# cruise.net
KiCad netlist of a schematic drawn in EAGLE
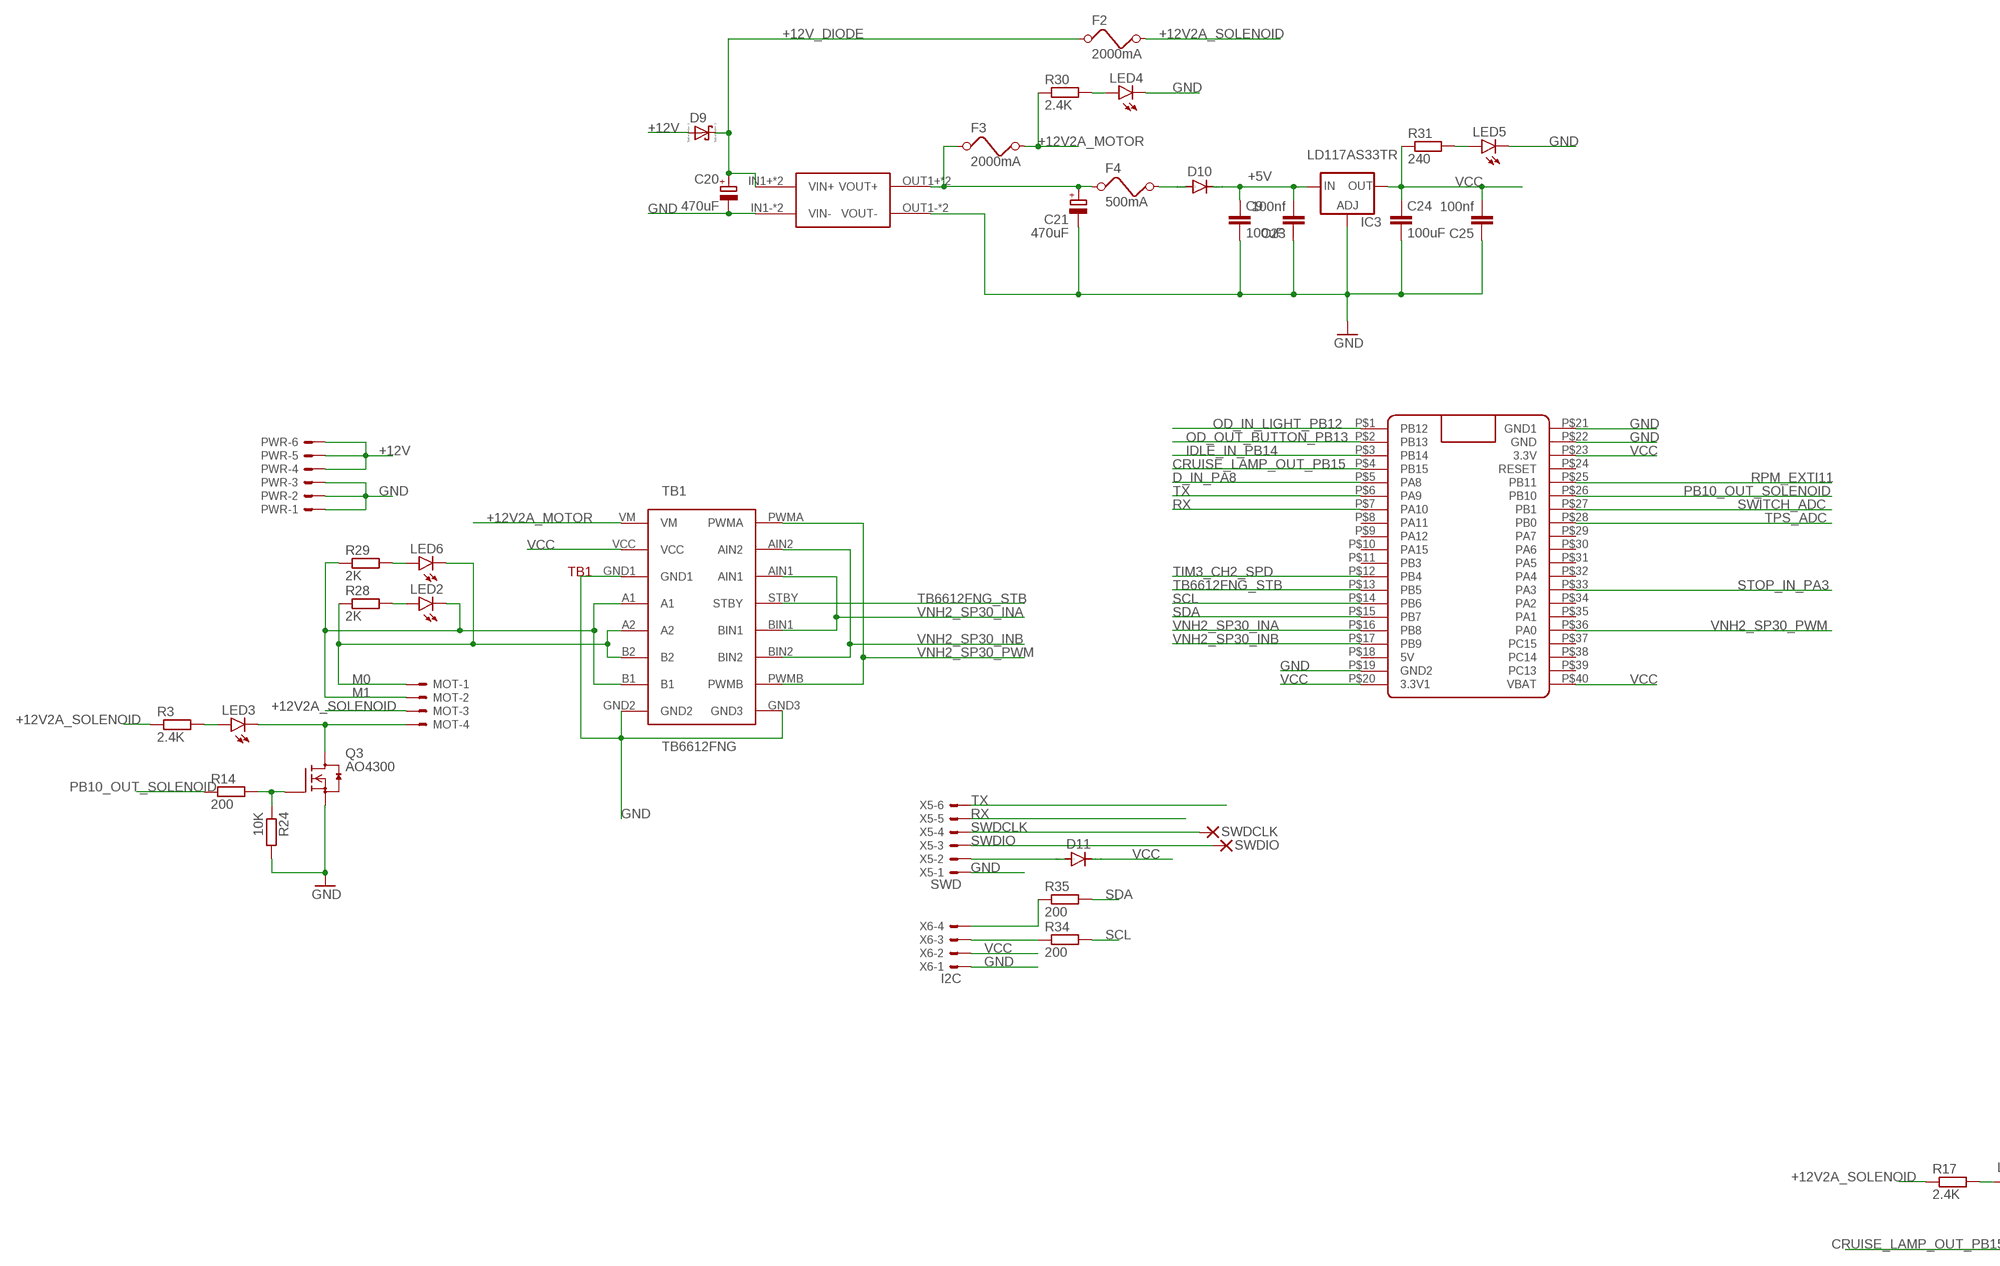
[diagram p0: schematic, sheet 1, part 1 of 2]
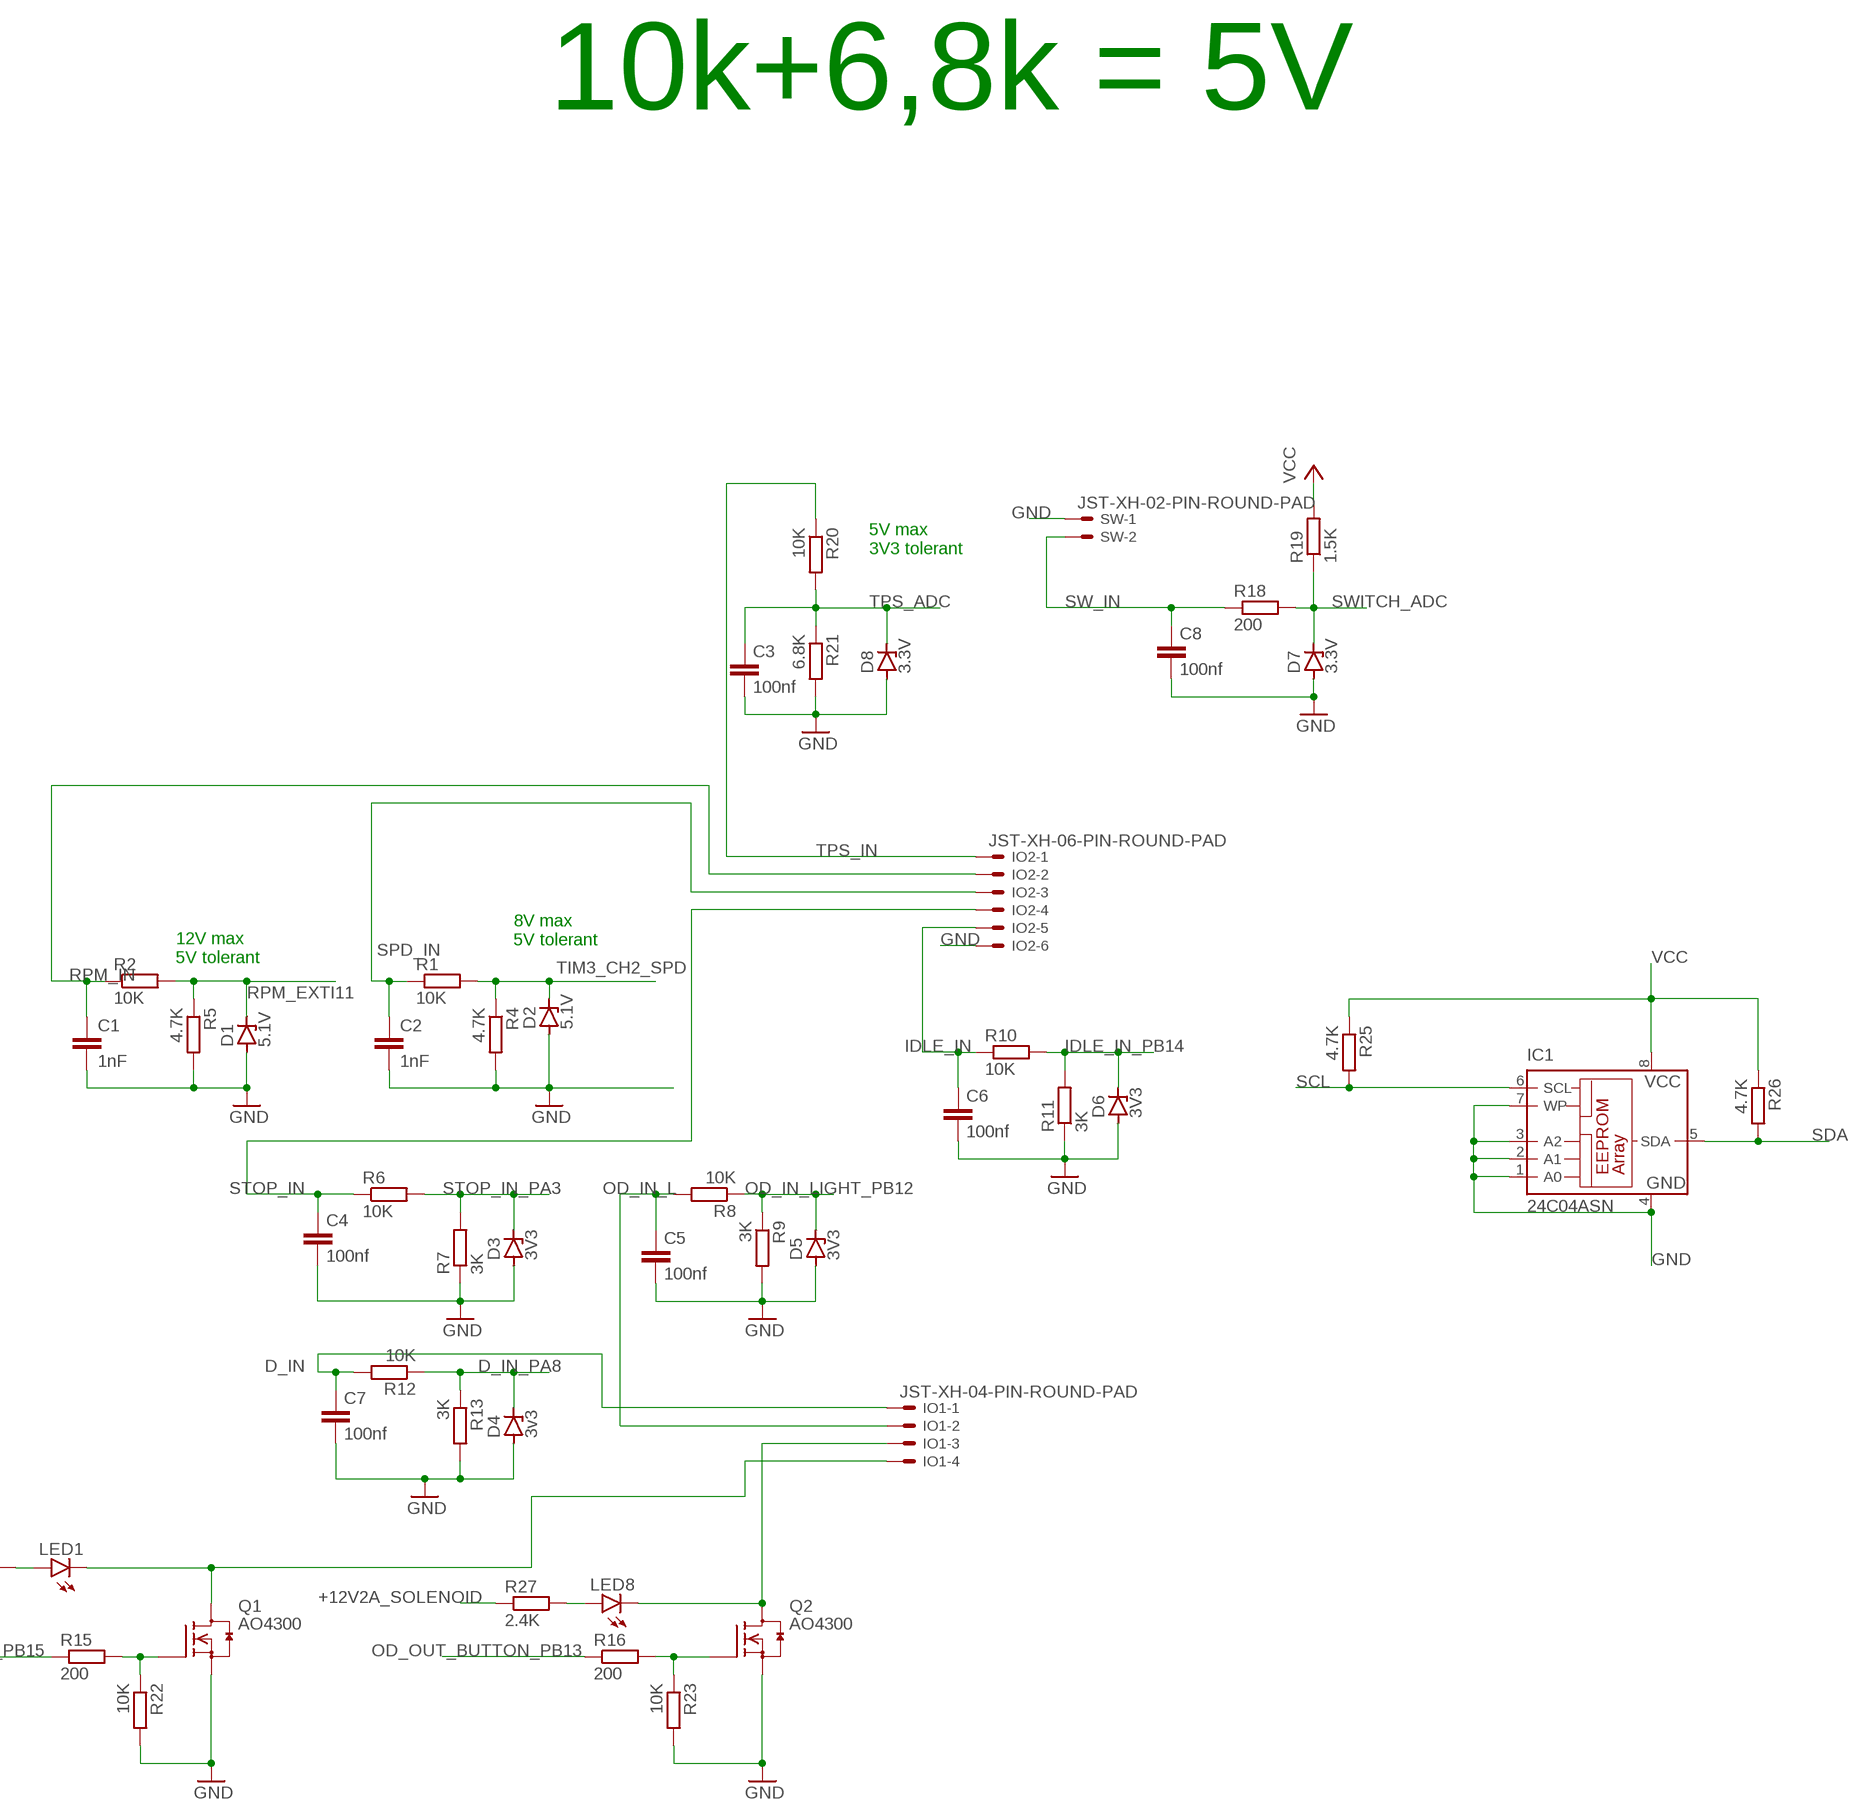
[diagram p1: schematic, sheet 1, part 2 of 2]

(export (version "E")
  (design (tool "Eeschema 10.0.6"))
  (components
    (comp (ref "C1")
      (value "1nF")
      (footprint "eagle-import:C0805K")
      (libsource (lib "eagle-import") (part "C-EUC0805K"))
    )
    (comp (ref "C2")
      (value "1nF")
      (footprint "eagle-import:C0805K")
      (libsource (lib "eagle-import") (part "C-EUC0805K"))
    )
    (comp (ref "C3")
      (value "100nf")
      (footprint "eagle-import:C0805K")
      (libsource (lib "eagle-import") (part "C-EUC0805K"))
    )
    (comp (ref "C4")
      (value "100nf")
      (footprint "eagle-import:C0805K")
      (libsource (lib "eagle-import") (part "C-EUC0805K"))
    )
    (comp (ref "C5")
      (value "100nf")
      (footprint "eagle-import:C0805K")
      (libsource (lib "eagle-import") (part "C-EUC0805K"))
    )
    (comp (ref "C6")
      (value "100nf")
      (footprint "eagle-import:C0805K")
      (libsource (lib "eagle-import") (part "C-EUC0805K"))
    )
    (comp (ref "C7")
      (value "100nf")
      (footprint "eagle-import:C0805K")
      (libsource (lib "eagle-import") (part "C-EUC0805K"))
    )
    (comp (ref "C8")
      (value "100nf")
      (footprint "eagle-import:C0805K")
      (libsource (lib "eagle-import") (part "C-EUC0805K"))
    )
    (comp (ref "C9")
      (value "100uF")
      (footprint "eagle-import:C1210")
      (libsource (lib "eagle-import") (part "resistor_348_C-EUC1210"))
    )
    (comp (ref "C20")
      (value "470uF")
      (footprint "eagle-import:PANASONIC_G")
      (libsource (lib "eagle-import") (part "CPOL-EUG"))
    )
    (comp (ref "C21")
      (value "470uF")
      (footprint "eagle-import:PANASONIC_G")
      (libsource (lib "eagle-import") (part "CPOL-EUG"))
    )
    (comp (ref "C23")
      (value "100nf")
      (footprint "eagle-import:C0805")
      (libsource (lib "eagle-import") (part "C-EUC0805"))
    )
    (comp (ref "C24")
      (value "100uF")
      (footprint "eagle-import:C1210")
      (libsource (lib "eagle-import") (part "resistor_348_C-EUC1210"))
    )
    (comp (ref "C25")
      (value "100nf")
      (footprint "eagle-import:C0805")
      (libsource (lib "eagle-import") (part "C-EUC0805"))
    )
    (comp (ref "D1")
      (value "5.1V")
      (footprint "eagle-import:SOD80C")
      (libsource (lib "eagle-import") (part "ZENER-DIODESOD80C"))
    )
    (comp (ref "D2")
      (value "5.1V")
      (footprint "eagle-import:SOD80C")
      (libsource (lib "eagle-import") (part "ZENER-DIODESOD80C"))
    )
    (comp (ref "D3")
      (value "3V3")
      (footprint "eagle-import:SOD80C")
      (libsource (lib "eagle-import") (part "ZENER-DIODESOD80C"))
    )
    (comp (ref "D4")
      (value "3v3")
      (footprint "eagle-import:SOD80C")
      (libsource (lib "eagle-import") (part "ZENER-DIODESOD80C"))
    )
    (comp (ref "D5")
      (value "3V3")
      (footprint "eagle-import:SOD80C")
      (libsource (lib "eagle-import") (part "ZENER-DIODESOD80C"))
    )
    (comp (ref "D6")
      (value "3V3")
      (footprint "eagle-import:SOD80C")
      (libsource (lib "eagle-import") (part "ZENER-DIODESOD80C"))
    )
    (comp (ref "D7")
      (value "3.3V")
      (footprint "eagle-import:SOD80C")
      (libsource (lib "eagle-import") (part "ZENER-DIODESOD80C"))
    )
    (comp (ref "D8")
      (value "3.3V")
      (footprint "eagle-import:SOD80C")
      (libsource (lib "eagle-import") (part "ZENER-DIODESOD80C"))
    )
    (comp (ref "D9")
      (value "SCHOTTKY-DIODESMC")
      (footprint "eagle-import:DIODE_SMC")
      (libsource (lib "eagle-import") (part "SCHOTTKY-DIODESMC"))
    )
    (comp (ref "D10")
      (value "DIODE-SOD323-W")
      (footprint "eagle-import:SOD323-W")
      (libsource (lib "eagle-import") (part "DIODE-SOD323-W"))
    )
    (comp (ref "D11")
      (value "DIODE-SOD323-W")
      (footprint "eagle-import:SOD323-W")
      (libsource (lib "eagle-import") (part "DIODE-SOD323-W"))
    )
    (comp (ref "F2")
      (value "2000mA")
      (footprint "eagle-import:1206")
      (libsource (lib "eagle-import") (part "FUSEC"))
    )
    (comp (ref "F3")
      (value "2000mA")
      (footprint "eagle-import:1206")
      (libsource (lib "eagle-import") (part "FUSEC"))
    )
    (comp (ref "F4")
      (value "500mA")
      (footprint "eagle-import:1206")
      (libsource (lib "eagle-import") (part "FUSEC"))
    )
    (comp (ref "IC1")
      (value "24C04ASN")
      (footprint "eagle-import:SO-08")
      (libsource (lib "eagle-import") (part "24CSN04A"))
    )
    (comp (ref "IC3")
      (value "LD117AS33TR")
      (footprint "eagle-import:SOT223")
      (libsource (lib "eagle-import") (part "LD117A?S33TR"))
    )
    (comp (ref "IO1")
      (value "JST-XH-04-PIN-ROUND-PAD")
      (footprint "eagle-import:JST-XH-04-PACKAGE-ROUND-PAD")
      (libsource (lib "eagle-import") (part "JST-XH-04-PIN-ROUND-PAD"))
    )
    (comp (ref "IO2")
      (value "JST-XH-06-PIN-ROUND-PAD")
      (footprint "eagle-import:JST-XH-06-PACKAGE-ROUND-PAD")
      (libsource (lib "eagle-import") (part "JST-XH-06-PIN-ROUND-PAD"))
    )
    (comp (ref "LED1")
      (value "LED3MM")
      (footprint "eagle-import:LED3MM")
      (libsource (lib "eagle-import") (part "LED3MM"))
    )
    (comp (ref "LED2")
      (value "LED3MM")
      (footprint "eagle-import:LED3MM")
      (libsource (lib "eagle-import") (part "LED3MM"))
    )
    (comp (ref "LED3")
      (value "LED3MM")
      (footprint "eagle-import:LED3MM")
      (libsource (lib "eagle-import") (part "LED3MM"))
    )
    (comp (ref "LED4")
      (value "LED3MM")
      (footprint "eagle-import:LED3MM")
      (libsource (lib "eagle-import") (part "LED3MM"))
    )
    (comp (ref "LED5")
      (value "LED3MM")
      (footprint "eagle-import:LED3MM")
      (libsource (lib "eagle-import") (part "LED3MM"))
    )
    (comp (ref "LED6")
      (value "LED3MM")
      (footprint "eagle-import:LED3MM")
      (libsource (lib "eagle-import") (part "LED3MM"))
    )
    (comp (ref "LED8")
      (value "LED3MM")
      (footprint "eagle-import:LED3MM")
      (libsource (lib "eagle-import") (part "LED3MM"))
    )
    (comp (ref "MOT")
      (value "JST-XH-04-PIN-LONG-PAD")
      (footprint "eagle-import:JST-XH-04-PACKAGE-LONG-PAD")
      (libsource (lib "eagle-import") (part "JST-XH-04-PIN-LONG-PAD"))
    )
    (comp (ref "PWR")
      (value "JST-XH-06-PIN-LONG-PAD")
      (footprint "eagle-import:JST-XH-06-PACKAGE-LONG-PAD")
      (libsource (lib "eagle-import") (part "JST-XH-06-PIN-LONG-PAD"))
    )
    (comp (ref "Q1")
      (value "AO4300")
      (footprint "eagle-import:SOT23")
      (libsource (lib "eagle-import") (part "BSS138"))
    )
    (comp (ref "Q2")
      (value "AO4300")
      (footprint "eagle-import:SOT23")
      (libsource (lib "eagle-import") (part "BSS138"))
    )
    (comp (ref "Q3")
      (value "AO4300")
      (footprint "eagle-import:SOT23")
      (libsource (lib "eagle-import") (part "BSS138"))
    )
    (comp (ref "R1")
      (value "10K")
      (footprint "eagle-import:R0805")
      (libsource (lib "eagle-import") (part "R-EU_R0805"))
    )
    (comp (ref "R2")
      (value "10K")
      (footprint "eagle-import:R0805")
      (libsource (lib "eagle-import") (part "R-EU_R0805"))
    )
    (comp (ref "R3")
      (value "2.4K")
      (footprint "eagle-import:R0805")
      (libsource (lib "eagle-import") (part "R-EU_R0805"))
    )
    (comp (ref "R4")
      (value "4.7K")
      (footprint "eagle-import:R0805")
      (libsource (lib "eagle-import") (part "R-EU_R0805"))
    )
    (comp (ref "R5")
      (value "4.7K")
      (footprint "eagle-import:R0805")
      (libsource (lib "eagle-import") (part "R-EU_R0805"))
    )
    (comp (ref "R6")
      (value "10K")
      (footprint "eagle-import:R0805")
      (libsource (lib "eagle-import") (part "R-EU_R0805"))
    )
    (comp (ref "R7")
      (value "3K")
      (footprint "eagle-import:R0805")
      (libsource (lib "eagle-import") (part "R-EU_R0805"))
    )
    (comp (ref "R8")
      (value "10K")
      (footprint "eagle-import:R0805")
      (libsource (lib "eagle-import") (part "R-EU_R0805"))
    )
    (comp (ref "R9")
      (value "3K")
      (footprint "eagle-import:R0805")
      (libsource (lib "eagle-import") (part "R-EU_R0805"))
    )
    (comp (ref "R10")
      (value "10K")
      (footprint "eagle-import:R0805")
      (libsource (lib "eagle-import") (part "R-EU_R0805"))
    )
    (comp (ref "R11")
      (value "3K")
      (footprint "eagle-import:R0805")
      (libsource (lib "eagle-import") (part "R-EU_R0805"))
    )
    (comp (ref "R12")
      (value "10K")
      (footprint "eagle-import:R0805")
      (libsource (lib "eagle-import") (part "R-EU_R0805"))
    )
    (comp (ref "R13")
      (value "3K")
      (footprint "eagle-import:R0805")
      (libsource (lib "eagle-import") (part "R-EU_R0805"))
    )
    (comp (ref "R14")
      (value "200")
      (footprint "eagle-import:R0805")
      (libsource (lib "eagle-import") (part "R-EU_R0805"))
    )
    (comp (ref "R15")
      (value "200")
      (footprint "eagle-import:R0805")
      (libsource (lib "eagle-import") (part "R-EU_R0805"))
    )
    (comp (ref "R16")
      (value "200")
      (footprint "eagle-import:R0805")
      (libsource (lib "eagle-import") (part "R-EU_R0805"))
    )
    (comp (ref "R17")
      (value "2.4K")
      (footprint "eagle-import:R0805")
      (libsource (lib "eagle-import") (part "R-EU_R0805"))
    )
    (comp (ref "R18")
      (value "200")
      (footprint "eagle-import:R0805")
      (libsource (lib "eagle-import") (part "R-EU_R0805"))
    )
    (comp (ref "R19")
      (value "1.5K")
      (footprint "eagle-import:R0805")
      (libsource (lib "eagle-import") (part "R-EU_R0805"))
    )
    (comp (ref "R20")
      (value "10K")
      (footprint "eagle-import:R0805")
      (libsource (lib "eagle-import") (part "R-EU_R0805"))
    )
    (comp (ref "R21")
      (value "6.8K")
      (footprint "eagle-import:R0805")
      (libsource (lib "eagle-import") (part "R-EU_R0805"))
    )
    (comp (ref "R22")
      (value "10K")
      (footprint "eagle-import:R0805")
      (libsource (lib "eagle-import") (part "R-EU_R0805"))
    )
    (comp (ref "R23")
      (value "10K")
      (footprint "eagle-import:R0805")
      (libsource (lib "eagle-import") (part "R-EU_R0805"))
    )
    (comp (ref "R24")
      (value "10K")
      (footprint "eagle-import:R0805")
      (libsource (lib "eagle-import") (part "R-EU_R0805"))
    )
    (comp (ref "R25")
      (value "4.7K")
      (footprint "eagle-import:R0805")
      (libsource (lib "eagle-import") (part "R-EU_R0805"))
    )
    (comp (ref "R26")
      (value "4.7K")
      (footprint "eagle-import:R0805")
      (libsource (lib "eagle-import") (part "R-EU_R0805"))
    )
    (comp (ref "R27")
      (value "2.4K")
      (footprint "eagle-import:R0805")
      (libsource (lib "eagle-import") (part "R-EU_R0805"))
    )
    (comp (ref "R28")
      (value "2K")
      (footprint "eagle-import:R0805")
      (libsource (lib "eagle-import") (part "R-EU_R0805"))
    )
    (comp (ref "R29")
      (value "2K")
      (footprint "eagle-import:R0805")
      (libsource (lib "eagle-import") (part "R-EU_R0805"))
    )
    (comp (ref "R30")
      (value "2.4K")
      (footprint "eagle-import:R0805")
      (libsource (lib "eagle-import") (part "R-EU_R0805"))
    )
    (comp (ref "R31")
      (value "240")
      (footprint "eagle-import:R0805")
      (libsource (lib "eagle-import") (part "R-EU_R0805"))
    )
    (comp (ref "R34")
      (value "200")
      (footprint "eagle-import:R0805")
      (libsource (lib "eagle-import") (part "R-EU_R0805"))
    )
    (comp (ref "R35")
      (value "200")
      (footprint "eagle-import:R0805")
      (libsource (lib "eagle-import") (part "R-EU_R0805"))
    )
    (comp (ref "SW")
      (value "JST-XH-02-PIN-ROUND-PAD")
      (footprint "eagle-import:JST-XH-02-PACKAGE-ROUND-PAD")
      (libsource (lib "eagle-import") (part "JST-XH-02-PIN-ROUND-PAD"))
    )
    (comp (ref "SWDCLK")
      (value "WIREPAD2,15/1,0")
      (footprint "eagle-import:2,15_1,0")
      (libsource (lib "eagle-import") (part "WIREPAD2,15/1,0"))
    )
    (comp (ref "SWDIO")
      (value "WIREPAD2,15/1,0")
      (footprint "eagle-import:2,15_1,0")
      (libsource (lib "eagle-import") (part "WIREPAD2,15/1,0"))
    )
    (comp (ref "TB1")
      (value "TB6612FNG")
      (footprint "eagle-import:TB6612FNG")
      (libsource (lib "eagle-import") (part "TB6612FNG"))
    )
    (comp (ref "U$1")
      (value "BLUE_PILL")
      (footprint "eagle-import:BLUE_PILL")
      (libsource (lib "eagle-import") (part "BLUE_PILL"))
    )
    (comp (ref "U$6")
      (value "MP1584")
      (footprint "eagle-import:DC-BRICK")
      (libsource (lib "eagle-import") (part "MP1584"))
    )
    (comp (ref "X5")
      (value "SWD")
      (footprint "eagle-import:JST-XH-06-PACKAGE-ROUND-PAD")
      (libsource (lib "eagle-import") (part "JST-XH-06-PIN-ROUND-PAD"))
    )
    (comp (ref "X6")
      (value "I2C")
      (footprint "eagle-import:JST-XH-04-PACKAGE-ROUND-PAD")
      (libsource (lib "eagle-import") (part "JST-XH-04-PIN-ROUND-PAD"))
    )
  )
  (nets
    (net (code "1") (name "/+5V") (class "Default")
      (node (ref "C23") (pin "2") (pinfunction "2_2") (pintype "passive"))
      (node (ref "C9") (pin "1") (pinfunction "1_1") (pintype "passive"))
      (node (ref "D10") (pin "C") (pinfunction "C_C") (pintype "passive"))
      (node (ref "IC3") (pin "3") (pinfunction "IN_3") (pintype "input"))
    )
    (net (code "2") (name "/+12V") (class "Default")
      (node (ref "D9") (pin "A") (pinfunction "C_A") (pintype "passive"))
      (node (ref "PWR") (pin "4") (pinfunction "S_4") (pintype "passive"))
      (node (ref "PWR") (pin "5") (pinfunction "S_5") (pintype "passive"))
      (node (ref "PWR") (pin "6") (pinfunction "S_6") (pintype "passive"))
    )
    (net (code "3") (name "/+12V2A_MOTOR") (class "Default")
      (node (ref "F3") (pin "2") (pinfunction "2_2") (pintype "passive"))
      (node (ref "R30") (pin "1") (pinfunction "1_1") (pintype "passive"))
      (node (ref "TB1") (pin "VM") (pinfunction "VM_VM") (pintype "bidirectional"))
    )
    (net (code "4") (name "/+12V2A_SOLENOID") (class "Default")
      (node (ref "F2") (pin "2") (pinfunction "2_2") (pintype "passive"))
      (node (ref "MOT") (pin "3") (pinfunction "S_3") (pintype "passive"))
      (node (ref "R17") (pin "1") (pinfunction "1_1") (pintype "passive"))
      (node (ref "R27") (pin "1") (pinfunction "1_1") (pintype "passive"))
      (node (ref "R3") (pin "1") (pinfunction "1_1") (pintype "passive"))
    )
    (net (code "5") (name "/+12V_DIODE") (class "Default")
      (node (ref "C20") (pin "+") (pinfunction "+_+") (pintype "passive"))
      (node (ref "D9") (pin "C") (pinfunction "A_C") (pintype "passive"))
      (node (ref "F2") (pin "1") (pinfunction "1_1") (pintype "passive"))
      (node (ref "U$6") (pin "IN1+") (pinfunction "VIN+_IN1+") (pintype "input"))
      (node (ref "U$6") (pin "IN2+") (pinfunction "VIN+_IN2+") (pintype "input"))
    )
    (net (code "6") (name "/CRUISE_LAMP_OUT_PB15") (class "Default")
      (node (ref "R15") (pin "1") (pinfunction "1_1") (pintype "passive"))
      (node (ref "U$1") (pin "P$4") (pinfunction "PB15_P$4") (pintype "bidirectional"))
    )
    (net (code "7") (name "/D_IN") (class "Default")
      (node (ref "C7") (pin "1") (pinfunction "1_1") (pintype "passive"))
      (node (ref "IO1") (pin "1") (pinfunction "S_1") (pintype "passive"))
      (node (ref "R12") (pin "2") (pinfunction "2_2") (pintype "passive"))
    )
    (net (code "8") (name "/D_IN_PA8") (class "Default")
      (node (ref "D4") (pin "C") (pinfunction "C_C") (pintype "passive"))
      (node (ref "R12") (pin "1") (pinfunction "1_1") (pintype "passive"))
      (node (ref "R13") (pin "1") (pinfunction "1_1") (pintype "passive"))
      (node (ref "U$1") (pin "P$5") (pinfunction "PA8_P$5") (pintype "bidirectional"))
    )
    (net (code "9") (name "/IDLE_IN") (class "Default")
      (node (ref "C6") (pin "1") (pinfunction "1_1") (pintype "passive"))
      (node (ref "IO2") (pin "5") (pinfunction "S_5") (pintype "passive"))
      (node (ref "R10") (pin "1") (pinfunction "1_1") (pintype "passive"))
    )
    (net (code "10") (name "/IDLE_IN_PB14") (class "Default")
      (node (ref "D6") (pin "C") (pinfunction "C_C") (pintype "passive"))
      (node (ref "R10") (pin "2") (pinfunction "2_2") (pintype "passive"))
      (node (ref "R11") (pin "2") (pinfunction "2_2") (pintype "passive"))
      (node (ref "U$1") (pin "P$3") (pinfunction "PB14_P$3") (pintype "bidirectional"))
    )
    (net (code "11") (name "/M0") (class "Default")
      (node (ref "LED6") (pin "K") (pinfunction "C_K") (pintype "passive"))
      (node (ref "MOT") (pin "1") (pinfunction "S_1") (pintype "passive"))
      (node (ref "R28") (pin "1") (pinfunction "1_1") (pintype "passive"))
      (node (ref "TB1") (pin "A2") (pinfunction "A2_A2") (pintype "bidirectional"))
      (node (ref "TB1") (pin "B2") (pinfunction "B2_B2") (pintype "bidirectional"))
    )
    (net (code "12") (name "/M1") (class "Default")
      (node (ref "LED2") (pin "K") (pinfunction "C_K") (pintype "passive"))
      (node (ref "MOT") (pin "2") (pinfunction "S_2") (pintype "passive"))
      (node (ref "R29") (pin "1") (pinfunction "1_1") (pintype "passive"))
      (node (ref "TB1") (pin "A1") (pinfunction "A1_A1") (pintype "bidirectional"))
      (node (ref "TB1") (pin "B1") (pinfunction "B1_B1") (pintype "bidirectional"))
    )
    (net (code "13") (name "/OD_IN_L") (class "Default")
      (node (ref "C5") (pin "1") (pinfunction "1_1") (pintype "passive"))
      (node (ref "IO1") (pin "2") (pinfunction "S_2") (pintype "passive"))
      (node (ref "R8") (pin "2") (pinfunction "2_2") (pintype "passive"))
    )
    (net (code "14") (name "/OD_IN_LIGHT_PB12") (class "Default")
      (node (ref "D5") (pin "C") (pinfunction "C_C") (pintype "passive"))
      (node (ref "R8") (pin "1") (pinfunction "1_1") (pintype "passive"))
      (node (ref "R9") (pin "1") (pinfunction "1_1") (pintype "passive"))
      (node (ref "U$1") (pin "P$1") (pinfunction "PB12_P$1") (pintype "bidirectional"))
    )
    (net (code "15") (name "/OD_OUT_BUTTON_PB13") (class "Default")
      (node (ref "R16") (pin "1") (pinfunction "1_1") (pintype "passive"))
      (node (ref "U$1") (pin "P$2") (pinfunction "PB13_P$2") (pintype "bidirectional"))
    )
    (net (code "16") (name "/PB10_OUT_SOLENOID") (class "Default")
      (node (ref "R14") (pin "1") (pinfunction "1_1") (pintype "passive"))
      (node (ref "U$1") (pin "P$26") (pinfunction "PB10_P$26") (pintype "bidirectional"))
    )
    (net (code "17") (name "/RPM_EXTI11") (class "Default")
      (node (ref "D1") (pin "C") (pinfunction "C_C") (pintype "passive"))
      (node (ref "R2") (pin "2") (pinfunction "2_2") (pintype "passive"))
      (node (ref "R5") (pin "1") (pinfunction "1_1") (pintype "passive"))
      (node (ref "U$1") (pin "P$25") (pinfunction "PB11_P$25") (pintype "bidirectional"))
    )
    (net (code "18") (name "/RPM_IN") (class "Default")
      (node (ref "C1") (pin "1") (pinfunction "1_1") (pintype "passive"))
      (node (ref "IO2") (pin "2") (pinfunction "S_2") (pintype "passive"))
      (node (ref "R2") (pin "1") (pinfunction "1_1") (pintype "passive"))
    )
    (net (code "19") (name "/RX") (class "Default")
      (node (ref "U$1") (pin "P$7") (pinfunction "PA10_P$7") (pintype "bidirectional"))
      (node (ref "X5") (pin "5") (pinfunction "S_5") (pintype "passive"))
    )
    (net (code "20") (name "/SCL") (class "Default")
      (node (ref "IC1") (pin "6") (pinfunction "SCL_6") (pintype "input"))
      (node (ref "R25") (pin "2") (pinfunction "2_2") (pintype "passive"))
      (node (ref "R34") (pin "2") (pinfunction "2_2") (pintype "passive"))
      (node (ref "U$1") (pin "P$14") (pinfunction "PB6_P$14") (pintype "bidirectional"))
    )
    (net (code "21") (name "/SDA") (class "Default")
      (node (ref "IC1") (pin "5") (pinfunction "SDA_5") (pintype "bidirectional"))
      (node (ref "R26") (pin "2") (pinfunction "2_2") (pintype "passive"))
      (node (ref "R35") (pin "2") (pinfunction "2_2") (pintype "passive"))
      (node (ref "U$1") (pin "P$15") (pinfunction "PB7_P$15") (pintype "bidirectional"))
    )
    (net (code "22") (name "/SPD_IN") (class "Default")
      (node (ref "C2") (pin "1") (pinfunction "1_1") (pintype "passive"))
      (node (ref "IO2") (pin "3") (pinfunction "S_3") (pintype "passive"))
      (node (ref "R1") (pin "1") (pinfunction "1_1") (pintype "passive"))
    )
    (net (code "23") (name "/STOP_IN") (class "Default")
      (node (ref "C4") (pin "1") (pinfunction "1_1") (pintype "passive"))
      (node (ref "IO2") (pin "4") (pinfunction "S_4") (pintype "passive"))
      (node (ref "R6") (pin "1") (pinfunction "1_1") (pintype "passive"))
    )
    (net (code "24") (name "/STOP_IN_PA3") (class "Default")
      (node (ref "D3") (pin "C") (pinfunction "C_C") (pintype "passive"))
      (node (ref "R6") (pin "2") (pinfunction "2_2") (pintype "passive"))
      (node (ref "R7") (pin "2") (pinfunction "2_2") (pintype "passive"))
      (node (ref "U$1") (pin "P$33") (pinfunction "PA3_P$33") (pintype "bidirectional"))
    )
    (net (code "25") (name "/SWDCLK") (class "Default")
      (node (ref "SWDCLK") (pin "1") (pinfunction "P_1") (pintype "passive"))
      (node (ref "X5") (pin "4") (pinfunction "S_4") (pintype "passive"))
    )
    (net (code "26") (name "/SWDIO") (class "Default")
      (node (ref "SWDIO") (pin "1") (pinfunction "P_1") (pintype "passive"))
      (node (ref "X5") (pin "3") (pinfunction "S_3") (pintype "passive"))
    )
    (net (code "27") (name "/SWITCH_ADC") (class "Default")
      (node (ref "D7") (pin "C") (pinfunction "C_C") (pintype "passive"))
      (node (ref "R18") (pin "2") (pinfunction "2_2") (pintype "passive"))
      (node (ref "R19") (pin "1") (pinfunction "1_1") (pintype "passive"))
      (node (ref "U$1") (pin "P$27") (pinfunction "PB1_P$27") (pintype "bidirectional"))
    )
    (net (code "28") (name "/SW_IN") (class "Default")
      (node (ref "C8") (pin "1") (pinfunction "1_1") (pintype "passive"))
      (node (ref "R18") (pin "1") (pinfunction "1_1") (pintype "passive"))
      (node (ref "SW") (pin "2") (pinfunction "S_2") (pintype "passive"))
    )
    (net (code "29") (name "/TB6612FNG_STB") (class "Default")
      (node (ref "TB1") (pin "STBY") (pinfunction "STBY_STBY") (pintype "bidirectional"))
      (node (ref "U$1") (pin "P$13") (pinfunction "PB5_P$13") (pintype "bidirectional"))
    )
    (net (code "30") (name "/TIM3_CH2_SPD") (class "Default")
      (node (ref "D2") (pin "C") (pinfunction "C_C") (pintype "passive"))
      (node (ref "R1") (pin "2") (pinfunction "2_2") (pintype "passive"))
      (node (ref "R4") (pin "1") (pinfunction "1_1") (pintype "passive"))
      (node (ref "U$1") (pin "P$12") (pinfunction "PB4_P$12") (pintype "bidirectional"))
    )
    (net (code "31") (name "/TPS_ADC") (class "Default")
      (node (ref "C3") (pin "1") (pinfunction "1_1") (pintype "passive"))
      (node (ref "D8") (pin "C") (pinfunction "C_C") (pintype "passive"))
      (node (ref "R20") (pin "2") (pinfunction "2_2") (pintype "passive"))
      (node (ref "R21") (pin "1") (pinfunction "1_1") (pintype "passive"))
      (node (ref "U$1") (pin "P$28") (pinfunction "PB0_P$28") (pintype "bidirectional"))
    )
    (net (code "32") (name "/TPS_IN") (class "Default")
      (node (ref "IO2") (pin "1") (pinfunction "S_1") (pintype "passive"))
      (node (ref "R20") (pin "1") (pinfunction "1_1") (pintype "passive"))
    )
    (net (code "33") (name "/TX") (class "Default")
      (node (ref "U$1") (pin "P$6") (pinfunction "PA9_P$6") (pintype "bidirectional"))
      (node (ref "X5") (pin "6") (pinfunction "S_6") (pintype "passive"))
    )
    (net (code "34") (name "/VNH2_SP30_INA") (class "Default")
      (node (ref "TB1") (pin "AIN1") (pinfunction "AIN1_AIN1") (pintype "bidirectional"))
      (node (ref "TB1") (pin "BIN1") (pinfunction "BIN1_BIN1") (pintype "bidirectional"))
      (node (ref "U$1") (pin "P$16") (pinfunction "PB8_P$16") (pintype "bidirectional"))
    )
    (net (code "35") (name "/VNH2_SP30_INB") (class "Default")
      (node (ref "TB1") (pin "AIN2") (pinfunction "AIN2_AIN2") (pintype "bidirectional"))
      (node (ref "TB1") (pin "BIN2") (pinfunction "BIN2_BIN2") (pintype "bidirectional"))
      (node (ref "U$1") (pin "P$17") (pinfunction "PB9_P$17") (pintype "bidirectional"))
    )
    (net (code "36") (name "/VNH2_SP30_PWM") (class "Default")
      (node (ref "TB1") (pin "PWMA") (pinfunction "PWMA_PWMA") (pintype "bidirectional"))
      (node (ref "TB1") (pin "PWMB") (pinfunction "PWMB_PWMB") (pintype "bidirectional"))
      (node (ref "U$1") (pin "P$36") (pinfunction "PA0_P$36") (pintype "bidirectional"))
    )
    (net (code "37") (name "GND") (class "Default")
      (node (ref "C1") (pin "2") (pinfunction "2_2") (pintype "passive"))
      (node (ref "C2") (pin "2") (pinfunction "2_2") (pintype "passive"))
      (node (ref "C20") (pin "-") (pinfunction "-_-") (pintype "passive"))
      (node (ref "C21") (pin "-") (pinfunction "-_-") (pintype "passive"))
      (node (ref "C23") (pin "1") (pinfunction "1_1") (pintype "passive"))
      (node (ref "C24") (pin "2") (pinfunction "2_2") (pintype "passive"))
      (node (ref "C25") (pin "1") (pinfunction "1_1") (pintype "passive"))
      (node (ref "C3") (pin "2") (pinfunction "2_2") (pintype "passive"))
      (node (ref "C4") (pin "2") (pinfunction "2_2") (pintype "passive"))
      (node (ref "C5") (pin "2") (pinfunction "2_2") (pintype "passive"))
      (node (ref "C6") (pin "2") (pinfunction "2_2") (pintype "passive"))
      (node (ref "C7") (pin "2") (pinfunction "2_2") (pintype "passive"))
      (node (ref "C8") (pin "2") (pinfunction "2_2") (pintype "passive"))
      (node (ref "C9") (pin "2") (pinfunction "2_2") (pintype "passive"))
      (node (ref "D1") (pin "A") (pinfunction "A_A") (pintype "passive"))
      (node (ref "D2") (pin "A") (pinfunction "A_A") (pintype "passive"))
      (node (ref "D3") (pin "A") (pinfunction "A_A") (pintype "passive"))
      (node (ref "D4") (pin "A") (pinfunction "A_A") (pintype "passive"))
      (node (ref "D5") (pin "A") (pinfunction "A_A") (pintype "passive"))
      (node (ref "D6") (pin "A") (pinfunction "A_A") (pintype "passive"))
      (node (ref "D7") (pin "A") (pinfunction "A_A") (pintype "passive"))
      (node (ref "D8") (pin "A") (pinfunction "A_A") (pintype "passive"))
      (node (ref "IC1") (pin "1") (pinfunction "A0_1") (pintype "input"))
      (node (ref "IC1") (pin "2") (pinfunction "A1_2") (pintype "input"))
      (node (ref "IC1") (pin "3") (pinfunction "A2_3") (pintype "input"))
      (node (ref "IC1") (pin "4") (pinfunction "GND_4") (pintype "power_in"))
      (node (ref "IC1") (pin "7") (pinfunction "WP_7") (pintype "input"))
      (node (ref "IC3") (pin "1") (pinfunction "ADJ_1") (pintype "input"))
      (node (ref "IO2") (pin "6") (pinfunction "S_6") (pintype "passive"))
      (node (ref "LED4") (pin "K") (pinfunction "C_K") (pintype "passive"))
      (node (ref "LED5") (pin "K") (pinfunction "C_K") (pintype "passive"))
      (node (ref "PWR") (pin "1") (pinfunction "S_1") (pintype "passive"))
      (node (ref "PWR") (pin "2") (pinfunction "S_2") (pintype "passive"))
      (node (ref "PWR") (pin "3") (pinfunction "S_3") (pintype "passive"))
      (node (ref "Q1") (pin "2") (pinfunction "S_2") (pintype "passive"))
      (node (ref "Q2") (pin "2") (pinfunction "S_2") (pintype "passive"))
      (node (ref "Q3") (pin "2") (pinfunction "S_2") (pintype "passive"))
      (node (ref "R11") (pin "1") (pinfunction "1_1") (pintype "passive"))
      (node (ref "R13") (pin "2") (pinfunction "2_2") (pintype "passive"))
      (node (ref "R21") (pin "2") (pinfunction "2_2") (pintype "passive"))
      (node (ref "R22") (pin "2") (pinfunction "2_2") (pintype "passive"))
      (node (ref "R23") (pin "2") (pinfunction "2_2") (pintype "passive"))
      (node (ref "R24") (pin "2") (pinfunction "2_2") (pintype "passive"))
      (node (ref "R4") (pin "2") (pinfunction "2_2") (pintype "passive"))
      (node (ref "R5") (pin "2") (pinfunction "2_2") (pintype "passive"))
      (node (ref "R7") (pin "1") (pinfunction "1_1") (pintype "passive"))
      (node (ref "R9") (pin "2") (pinfunction "2_2") (pintype "passive"))
      (node (ref "SW") (pin "1") (pinfunction "S_1") (pintype "passive"))
      (node (ref "TB1") (pin "GND1") (pinfunction "GND1_GND1") (pintype "bidirectional"))
      (node (ref "TB1") (pin "GND2") (pinfunction "GND2_GND2") (pintype "bidirectional"))
      (node (ref "TB1") (pin "GND3") (pinfunction "GND3_GND3") (pintype "bidirectional"))
      (node (ref "U$1") (pin "P$19") (pinfunction "GND2_P$19") (pintype "bidirectional"))
      (node (ref "U$1") (pin "P$21") (pinfunction "GND1_P$21") (pintype "power_in"))
      (node (ref "U$1") (pin "P$22") (pinfunction "GND_P$22") (pintype "bidirectional"))
      (node (ref "U$6") (pin "IN1-") (pinfunction "VIN-_IN1-") (pintype "input"))
      (node (ref "U$6") (pin "IN2-") (pinfunction "VIN-_IN2-") (pintype "input"))
      (node (ref "U$6") (pin "OUT1-") (pinfunction "VOUT-_OUT1-") (pintype "output"))
      (node (ref "U$6") (pin "OUT2-") (pinfunction "VOUT-_OUT2-") (pintype "output"))
      (node (ref "X5") (pin "1") (pinfunction "S_1") (pintype "passive"))
      (node (ref "X6") (pin "1") (pinfunction "S_1") (pintype "passive"))
    )
    (net (code "38") (name "Net-(C21-Pad+)") (class "Default")
      (node (ref "C21") (pin "+") (pinfunction "+_+") (pintype "passive"))
      (node (ref "F3") (pin "1") (pinfunction "1_1") (pintype "passive"))
      (node (ref "F4") (pin "1") (pinfunction "1_1") (pintype "passive"))
      (node (ref "U$6") (pin "OUT1+") (pinfunction "VOUT+_OUT1+") (pintype "output"))
      (node (ref "U$6") (pin "OUT2+") (pinfunction "VOUT+_OUT2+") (pintype "output"))
    )
    (net (code "39") (name "Net-(D10-PadA)") (class "Default")
      (node (ref "D10") (pin "A") (pinfunction "A_A") (pintype "passive"))
      (node (ref "F4") (pin "2") (pinfunction "2_2") (pintype "passive"))
    )
    (net (code "40") (name "Net-(IO1C-S)") (class "Default")
      (node (ref "IO1") (pin "3") (pinfunction "S_3") (pintype "passive"))
      (node (ref "LED8") (pin "K") (pinfunction "C_K") (pintype "passive"))
      (node (ref "Q2") (pin "3") (pinfunction "D_3") (pintype "passive"))
    )
    (net (code "41") (name "Net-(IO1D-S)") (class "Default")
      (node (ref "IO1") (pin "4") (pinfunction "S_4") (pintype "passive"))
      (node (ref "LED1") (pin "K") (pinfunction "C_K") (pintype "passive"))
      (node (ref "Q1") (pin "3") (pinfunction "D_3") (pintype "passive"))
    )
    (net (code "42") (name "Net-(LED1-PadA)") (class "Default")
      (node (ref "LED1") (pin "A") (pinfunction "A_A") (pintype "passive"))
      (node (ref "R17") (pin "2") (pinfunction "2_2") (pintype "passive"))
    )
    (net (code "43") (name "Net-(LED2-PadA)") (class "Default")
      (node (ref "LED2") (pin "A") (pinfunction "A_A") (pintype "passive"))
      (node (ref "R28") (pin "2") (pinfunction "2_2") (pintype "passive"))
    )
    (net (code "44") (name "Net-(LED3-C)") (class "Default")
      (node (ref "LED3") (pin "K") (pinfunction "C_K") (pintype "passive"))
      (node (ref "MOT") (pin "4") (pinfunction "S_4") (pintype "passive"))
      (node (ref "Q3") (pin "3") (pinfunction "D_3") (pintype "passive"))
    )
    (net (code "45") (name "Net-(LED3-PadA)") (class "Default")
      (node (ref "LED3") (pin "A") (pinfunction "A_A") (pintype "passive"))
      (node (ref "R3") (pin "2") (pinfunction "2_2") (pintype "passive"))
    )
    (net (code "46") (name "Net-(LED4-PadA)") (class "Default")
      (node (ref "LED4") (pin "A") (pinfunction "A_A") (pintype "passive"))
      (node (ref "R30") (pin "2") (pinfunction "2_2") (pintype "passive"))
    )
    (net (code "47") (name "Net-(LED5-PadA)") (class "Default")
      (node (ref "LED5") (pin "A") (pinfunction "A_A") (pintype "passive"))
      (node (ref "R31") (pin "2") (pinfunction "2_2") (pintype "passive"))
    )
    (net (code "48") (name "Net-(LED6-PadA)") (class "Default")
      (node (ref "LED6") (pin "A") (pinfunction "A_A") (pintype "passive"))
      (node (ref "R29") (pin "2") (pinfunction "2_2") (pintype "passive"))
    )
    (net (code "49") (name "Net-(LED8-PadA)") (class "Default")
      (node (ref "LED8") (pin "A") (pinfunction "A_A") (pintype "passive"))
      (node (ref "R27") (pin "2") (pinfunction "2_2") (pintype "passive"))
    )
    (net (code "50") (name "Net-(Q1-G)") (class "Default")
      (node (ref "Q1") (pin "1") (pinfunction "G_1") (pintype "passive"))
      (node (ref "R15") (pin "2") (pinfunction "2_2") (pintype "passive"))
      (node (ref "R22") (pin "1") (pinfunction "1_1") (pintype "passive"))
    )
    (net (code "51") (name "Net-(Q2-G)") (class "Default")
      (node (ref "Q2") (pin "1") (pinfunction "G_1") (pintype "passive"))
      (node (ref "R16") (pin "2") (pinfunction "2_2") (pintype "passive"))
      (node (ref "R23") (pin "1") (pinfunction "1_1") (pintype "passive"))
    )
    (net (code "52") (name "Net-(Q3-G)") (class "Default")
      (node (ref "Q3") (pin "1") (pinfunction "G_1") (pintype "passive"))
      (node (ref "R14") (pin "2") (pinfunction "2_2") (pintype "passive"))
      (node (ref "R24") (pin "1") (pinfunction "1_1") (pintype "passive"))
    )
    (net (code "53") (name "Net-(X5B-S)") (class "Default")
      (node (ref "D11") (pin "A") (pinfunction "A_A") (pintype "passive"))
      (node (ref "X5") (pin "2") (pinfunction "S_2") (pintype "passive"))
    )
    (net (code "54") (name "Net-(X6C-S)") (class "Default")
      (node (ref "R34") (pin "1") (pinfunction "1_1") (pintype "passive"))
      (node (ref "X6") (pin "3") (pinfunction "S_3") (pintype "passive"))
    )
    (net (code "55") (name "Net-(X6D-S)") (class "Default")
      (node (ref "R35") (pin "1") (pinfunction "1_1") (pintype "passive"))
      (node (ref "X6") (pin "4") (pinfunction "S_4") (pintype "passive"))
    )
    (net (code "56") (name "VCC") (class "Default")
      (node (ref "C24") (pin "1") (pinfunction "1_1") (pintype "passive"))
      (node (ref "C25") (pin "2") (pinfunction "2_2") (pintype "passive"))
      (node (ref "D11") (pin "C") (pinfunction "C_C") (pintype "passive"))
      (node (ref "IC1") (pin "8") (pinfunction "VCC_8") (pintype "power_in"))
      (node (ref "IC3") (pin "4") (pinfunction "OUT_4") (pintype "passive"))
      (node (ref "R19") (pin "2") (pinfunction "2_2") (pintype "passive"))
      (node (ref "R25") (pin "1") (pinfunction "1_1") (pintype "passive"))
      (node (ref "R26") (pin "1") (pinfunction "1_1") (pintype "passive"))
      (node (ref "R31") (pin "1") (pinfunction "1_1") (pintype "passive"))
      (node (ref "TB1") (pin "VCC") (pinfunction "VCC_VCC") (pintype "bidirectional"))
      (node (ref "U$1") (pin "P$20") (pinfunction "3.3V1_P$20") (pintype "bidirectional"))
      (node (ref "U$1") (pin "P$23") (pinfunction "3.3V_P$23") (pintype "bidirectional"))
      (node (ref "U$1") (pin "P$40") (pinfunction "VBAT_P$40") (pintype "bidirectional"))
      (node (ref "X6") (pin "2") (pinfunction "S_2") (pintype "passive"))
    )
    (net (code "57") (name "unconnected-(U$1-5V-PadP$18)") (class "Default")
      (node (ref "U$1") (pin "P$18") (pinfunction "5V_P$18") (pintype "bidirectional"))
    )
    (net (code "58") (name "unconnected-(U$1-PA1-PadP$35)") (class "Default")
      (node (ref "U$1") (pin "P$35") (pinfunction "PA1_P$35") (pintype "bidirectional"))
    )
    (net (code "59") (name "unconnected-(U$1-PA2-PadP$34)") (class "Default")
      (node (ref "U$1") (pin "P$34") (pinfunction "PA2_P$34") (pintype "bidirectional"))
    )
    (net (code "60") (name "unconnected-(U$1-PA4-PadP$32)") (class "Default")
      (node (ref "U$1") (pin "P$32") (pinfunction "PA4_P$32") (pintype "bidirectional"))
    )
    (net (code "61") (name "unconnected-(U$1-PA5-PadP$31)") (class "Default")
      (node (ref "U$1") (pin "P$31") (pinfunction "PA5_P$31") (pintype "bidirectional"))
    )
    (net (code "62") (name "unconnected-(U$1-PA6-PadP$30)") (class "Default")
      (node (ref "U$1") (pin "P$30") (pinfunction "PA6_P$30") (pintype "bidirectional"))
    )
    (net (code "63") (name "unconnected-(U$1-PA7-PadP$29)") (class "Default")
      (node (ref "U$1") (pin "P$29") (pinfunction "PA7_P$29") (pintype "bidirectional"))
    )
    (net (code "64") (name "unconnected-(U$1-PA11-PadP$8)") (class "Default")
      (node (ref "U$1") (pin "P$8") (pinfunction "PA11_P$8") (pintype "bidirectional"))
    )
    (net (code "65") (name "unconnected-(U$1-PA12-PadP$9)") (class "Default")
      (node (ref "U$1") (pin "P$9") (pinfunction "PA12_P$9") (pintype "bidirectional"))
    )
    (net (code "66") (name "unconnected-(U$1-PA15-PadP$10)") (class "Default")
      (node (ref "U$1") (pin "P$10") (pinfunction "PA15_P$10") (pintype "bidirectional"))
    )
    (net (code "67") (name "unconnected-(U$1-PB3-PadP$11)") (class "Default")
      (node (ref "U$1") (pin "P$11") (pinfunction "PB3_P$11") (pintype "bidirectional"))
    )
    (net (code "68") (name "unconnected-(U$1-PC13-PadP$39)") (class "Default")
      (node (ref "U$1") (pin "P$39") (pinfunction "PC13_P$39") (pintype "bidirectional"))
    )
    (net (code "69") (name "unconnected-(U$1-PC14-PadP$38)") (class "Default")
      (node (ref "U$1") (pin "P$38") (pinfunction "PC14_P$38") (pintype "bidirectional"))
    )
    (net (code "70") (name "unconnected-(U$1-PC15-PadP$37)") (class "Default")
      (node (ref "U$1") (pin "P$37") (pinfunction "PC15_P$37") (pintype "bidirectional"))
    )
    (net (code "71") (name "unconnected-(U$1-RESET-PadP$24)") (class "Default")
      (node (ref "U$1") (pin "P$24") (pinfunction "RESET_P$24") (pintype "bidirectional"))
    )
  )
)
